# MicroUSB.net
KiCad netlist of a schematic drawn in EAGLE
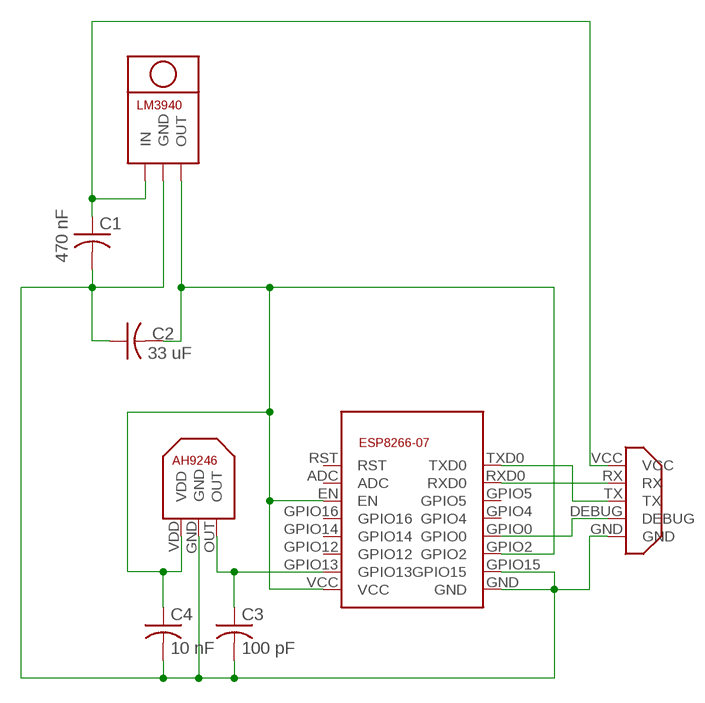
[diagram p0: schematic, sheet 1]

(export (version "E")
  (design (tool "Eeschema 10.0.6"))
  (components
    (comp (ref "C1")
      (value "470 nF")
      (footprint "eagle-import:C025-050X050")
      (libsource (lib "eagle-import") (part "C-US025-050X050"))
    )
    (comp (ref "C2")
      (value "33 uF")
      (footprint "eagle-import:C025-050X050")
      (libsource (lib "eagle-import") (part "C-US025-050X050"))
    )
    (comp (ref "C3")
      (value "100 pF")
      (footprint "eagle-import:C025-050X050")
      (libsource (lib "eagle-import") (part "C-US025-050X050"))
    )
    (comp (ref "C4")
      (value "10 nF")
      (footprint "eagle-import:C025-050X050")
      (libsource (lib "eagle-import") (part "C-US025-050X050"))
    )
    (comp (ref "U$1")
      (value "ESP8266-07")
      (footprint "eagle-import:ESP8266-07")
      (libsource (lib "eagle-import") (part "ESP8266-07"))
    )
    (comp (ref "U$2")
      (value "LM3940")
      (footprint "eagle-import:LM3940")
      (libsource (lib "eagle-import") (part "LM3940"))
    )
    (comp (ref "U$3")
      (value "AH9246")
      (footprint "eagle-import:AH9246")
      (libsource (lib "eagle-import") (part "AH9246"))
    )
    (comp (ref "U$4")
      (value "MICROUSB")
      (footprint "eagle-import:MICROUSB")
      (libsource (lib "eagle-import") (part "MICROUSB"))
    )
  )
  (nets
    (net (code "1") (name "Net-(C1-Pad1)") (class "Default")
      (node (ref "C1") (pin "1") (pinfunction "1_1") (pintype "passive"))
      (node (ref "U$2") (pin "IN") (pinfunction "IN_IN") (pintype "input"))
      (node (ref "U$4") (pin "VCC") (pinfunction "VCC_VCC") (pintype "power_in"))
    )
    (net (code "2") (name "Net-(C1-Pad2)") (class "Default")
      (node (ref "C1") (pin "2") (pinfunction "2_2") (pintype "passive"))
      (node (ref "C2") (pin "1") (pinfunction "1_1") (pintype "passive"))
      (node (ref "C3") (pin "2") (pinfunction "2_2") (pintype "passive"))
      (node (ref "C4") (pin "2") (pinfunction "2_2") (pintype "passive"))
      (node (ref "U$1") (pin "GND") (pinfunction "GND_GND") (pintype "power_in"))
      (node (ref "U$1") (pin "GPIO15") (pinfunction "GPIO15_GPIO15") (pintype "bidirectional"))
      (node (ref "U$2") (pin "GND") (pinfunction "GND_GND") (pintype "power_in"))
      (node (ref "U$3") (pin "GND") (pinfunction "GND_GND") (pintype "power_in"))
      (node (ref "U$4") (pin "GND") (pinfunction "GND_GND") (pintype "power_in"))
    )
    (net (code "3") (name "Net-(C2-Pad2)") (class "Default")
      (node (ref "C2") (pin "2") (pinfunction "2_2") (pintype "passive"))
      (node (ref "C4") (pin "1") (pinfunction "1_1") (pintype "passive"))
      (node (ref "U$1") (pin "EN") (pinfunction "EN_EN") (pintype "input"))
      (node (ref "U$1") (pin "GPIO2") (pinfunction "GPIO2_GPIO2") (pintype "bidirectional"))
      (node (ref "U$1") (pin "VCC") (pinfunction "VCC_VCC") (pintype "power_in"))
      (node (ref "U$2") (pin "OUT") (pinfunction "OUT_OUT") (pintype "output"))
      (node (ref "U$3") (pin "VDD") (pinfunction "VDD_VDD") (pintype "power_in"))
    )
    (net (code "4") (name "Net-(C3-Pad1)") (class "Default")
      (node (ref "C3") (pin "1") (pinfunction "1_1") (pintype "passive"))
      (node (ref "U$1") (pin "GPIO13") (pinfunction "GPIO13_GPIO13") (pintype "bidirectional"))
      (node (ref "U$3") (pin "OUT") (pinfunction "OUT_OUT") (pintype "output"))
    )
    (net (code "5") (name "Net-(U$1-PadGPIO0)") (class "Default")
      (node (ref "U$1") (pin "GPIO0") (pinfunction "GPIO0_GPIO0") (pintype "bidirectional"))
      (node (ref "U$4") (pin "DEBUG") (pinfunction "DEBUG_DEBUG") (pintype "bidirectional"))
    )
    (net (code "6") (name "Net-(U$1-PadRXD0)") (class "Default")
      (node (ref "U$1") (pin "RXD0") (pinfunction "RXD0_RXD0") (pintype "bidirectional"))
      (node (ref "U$4") (pin "RX") (pinfunction "RX_RX") (pintype "bidirectional"))
    )
    (net (code "7") (name "Net-(U$1-PadTXD0)") (class "Default")
      (node (ref "U$1") (pin "TXD0") (pinfunction "TXD0_TXD0") (pintype "bidirectional"))
      (node (ref "U$4") (pin "TX") (pinfunction "TX_TX") (pintype "bidirectional"))
    )
    (net (code "8") (name "unconnected-(U$1-PadADC)") (class "Default")
      (node (ref "U$1") (pin "ADC") (pinfunction "ADC_ADC") (pintype "input"))
    )
    (net (code "9") (name "unconnected-(U$1-PadGPIO4)") (class "Default")
      (node (ref "U$1") (pin "GPIO4") (pinfunction "GPIO4_GPIO4") (pintype "bidirectional"))
    )
    (net (code "10") (name "unconnected-(U$1-PadGPIO5)") (class "Default")
      (node (ref "U$1") (pin "GPIO5") (pinfunction "GPIO5_GPIO5") (pintype "bidirectional"))
    )
    (net (code "11") (name "unconnected-(U$1-PadGPIO12)") (class "Default")
      (node (ref "U$1") (pin "GPIO12") (pinfunction "GPIO12_GPIO12") (pintype "bidirectional"))
    )
    (net (code "12") (name "unconnected-(U$1-PadGPIO14)") (class "Default")
      (node (ref "U$1") (pin "GPIO14") (pinfunction "GPIO14_GPIO14") (pintype "bidirectional"))
    )
    (net (code "13") (name "unconnected-(U$1-PadGPIO16)") (class "Default")
      (node (ref "U$1") (pin "GPIO16") (pinfunction "GPIO16_GPIO16") (pintype "bidirectional"))
    )
    (net (code "14") (name "unconnected-(U$1-PadRST)") (class "Default")
      (node (ref "U$1") (pin "RST") (pinfunction "RST_RST") (pintype "input"))
    )
  )
)
